# SheetMotor.net
KiCad netlist of a schematic drawn in Altium Designer
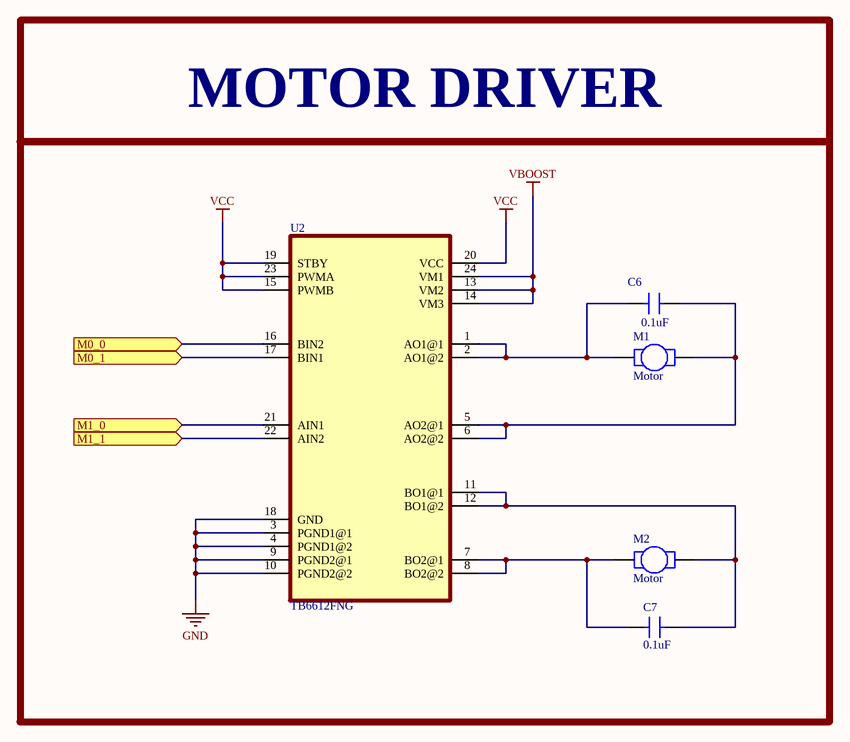
[diagram p0: SheetMotor.SchDoc]

(export (version "E")
  (design (tool "Eeschema 10.0.6"))
  (components
    (comp (ref "C6")
      (value "0.1uF")
      (footprint "CAP104 0.1UF 50V")
      (description "Cap Ceramic 0.1uF 50V X7R 10% SMD 2.0 x 1.2 mm 125 C Paper T/R")
      (fields
        (field (name "MANUFACTURER") "KEMET")
        (field (name "MANUFACTURER PART NUMBER") "C0805C104K5RACTU")
      )
      (libsource (lib "SchlibRobotLine") (part "C0805C104K5RACTU"))
    )
    (comp (ref "C7")
      (value "0.1uF")
      (footprint "CAP104 0.1UF 50V")
      (description "Cap Ceramic 0.1uF 50V X7R 10% SMD 2.0 x 1.2 mm 125 C Paper T/R")
      (fields
        (field (name "MANUFACTURER") "KEMET")
        (field (name "MANUFACTURER PART NUMBER") "C0805C104K5RACTU")
      )
      (libsource (lib "SchlibRobotLine") (part "C0805C104K5RACTU"))
    )
    (comp (ref "M1")
      (value "Motor")
      (footprint "motor")
      (description "298:1 MICRO METAL GEAR MOTOR STALL TORQUE @ 6V 46 OZ-IN")
      (fields (field (name "MANUFACTURER") "Pololu") (field (name "MANUFACTURER PART NUMBER") "2371"))
      (libsource (lib "SchlibRobotLine") (part "2371"))
    )
    (comp (ref "M2")
      (value "Motor")
      (footprint "motor")
      (description "298:1 MICRO METAL GEAR MOTOR STALL TORQUE @ 6V 46 OZ-IN")
      (fields (field (name "MANUFACTURER") "Pololu") (field (name "MANUFACTURER PART NUMBER") "2371"))
      (libsource (lib "SchlibRobotLine") (part "2371"))
    )
    (comp (ref "U2")
      (value "TB6612FNG")
      (footprint "SOP65P760X160-24N")
      (description "IC MOTOR DRIVER PAR 24SSOP")
      (fields
        (field (name "MANUFACTURER") "Toshiba")
        (field (name "MANUFACTURER PART NUMBER") "TB6612FNG,C,8,EL")
      )
      (libsource (lib "SchlibRobotLine") (part "TB6612FNG,C,8,EL"))
    )
  )
  (nets
    (net (code "1") (name "/M0_0") (class "Default")
      (node (ref "U2") (pin "16") (pinfunction "BIN2_16") (pintype "passive"))
    )
    (net (code "2") (name "/M0_1") (class "Default")
      (node (ref "U2") (pin "17") (pinfunction "BIN1_17") (pintype "passive"))
    )
    (net (code "3") (name "/M1_0") (class "Default")
      (node (ref "U2") (pin "21") (pinfunction "AIN1_21") (pintype "passive"))
    )
    (net (code "4") (name "/M1_1") (class "Default")
      (node (ref "U2") (pin "22") (pinfunction "AIN2_22") (pintype "passive"))
    )
    (net (code "5") (name "GND") (class "Default")
      (node (ref "U2") (pin "10") (pinfunction "PGND2@2_10") (pintype "passive"))
      (node (ref "U2") (pin "18") (pinfunction "GND_18") (pintype "passive"))
      (node (ref "U2") (pin "3") (pinfunction "PGND1@1_3") (pintype "passive"))
      (node (ref "U2") (pin "4") (pinfunction "PGND1@2_4") (pintype "passive"))
      (node (ref "U2") (pin "9") (pinfunction "PGND2@1_9") (pintype "passive"))
    )
    (net (code "6") (name "Net-(U2-AO1@1)") (class "Default")
      (node (ref "C6") (pin "1") (pinfunction "1_1") (pintype "passive"))
      (node (ref "M1") (pin "1") (pinfunction "1_1") (pintype "passive"))
      (node (ref "U2") (pin "1") (pinfunction "AO1@1_1") (pintype "passive"))
      (node (ref "U2") (pin "2") (pinfunction "AO1@2_2") (pintype "passive"))
    )
    (net (code "7") (name "Net-(U2-AO2@1)") (class "Default")
      (node (ref "C6") (pin "2") (pinfunction "2_2") (pintype "passive"))
      (node (ref "M1") (pin "2") (pinfunction "2_2") (pintype "passive"))
      (node (ref "U2") (pin "5") (pinfunction "AO2@1_5") (pintype "passive"))
      (node (ref "U2") (pin "6") (pinfunction "AO2@2_6") (pintype "passive"))
    )
    (net (code "8") (name "Net-(U2-BO1@1)") (class "Default")
      (node (ref "C7") (pin "2") (pinfunction "2_2") (pintype "passive"))
      (node (ref "M2") (pin "1") (pinfunction "1_1") (pintype "passive"))
      (node (ref "U2") (pin "11") (pinfunction "BO1@1_11") (pintype "passive"))
      (node (ref "U2") (pin "12") (pinfunction "BO1@2_12") (pintype "passive"))
    )
    (net (code "9") (name "Net-(U2-BO2@1)") (class "Default")
      (node (ref "C7") (pin "1") (pinfunction "1_1") (pintype "passive"))
      (node (ref "M2") (pin "2") (pinfunction "2_2") (pintype "passive"))
      (node (ref "U2") (pin "7") (pinfunction "BO2@1_7") (pintype "passive"))
      (node (ref "U2") (pin "8") (pinfunction "BO2@2_8") (pintype "passive"))
    )
    (net (code "10") (name "VBOOST") (class "Default")
      (node (ref "U2") (pin "13") (pinfunction "VM2_13") (pintype "power_in"))
      (node (ref "U2") (pin "14") (pinfunction "VM3_14") (pintype "power_in"))
      (node (ref "U2") (pin "24") (pinfunction "VM1_24") (pintype "power_in"))
    )
    (net (code "11") (name "VCC") (class "Default")
      (node (ref "U2") (pin "15") (pinfunction "PWMB_15") (pintype "passive"))
      (node (ref "U2") (pin "19") (pinfunction "STBY_19") (pintype "passive"))
      (node (ref "U2") (pin "20") (pinfunction "VCC_20") (pintype "power_in"))
      (node (ref "U2") (pin "23") (pinfunction "PWMA_23") (pintype "passive"))
    )
  )
)
